# Sensor_Board.net
KiCad netlist of a schematic drawn in Altium Designer
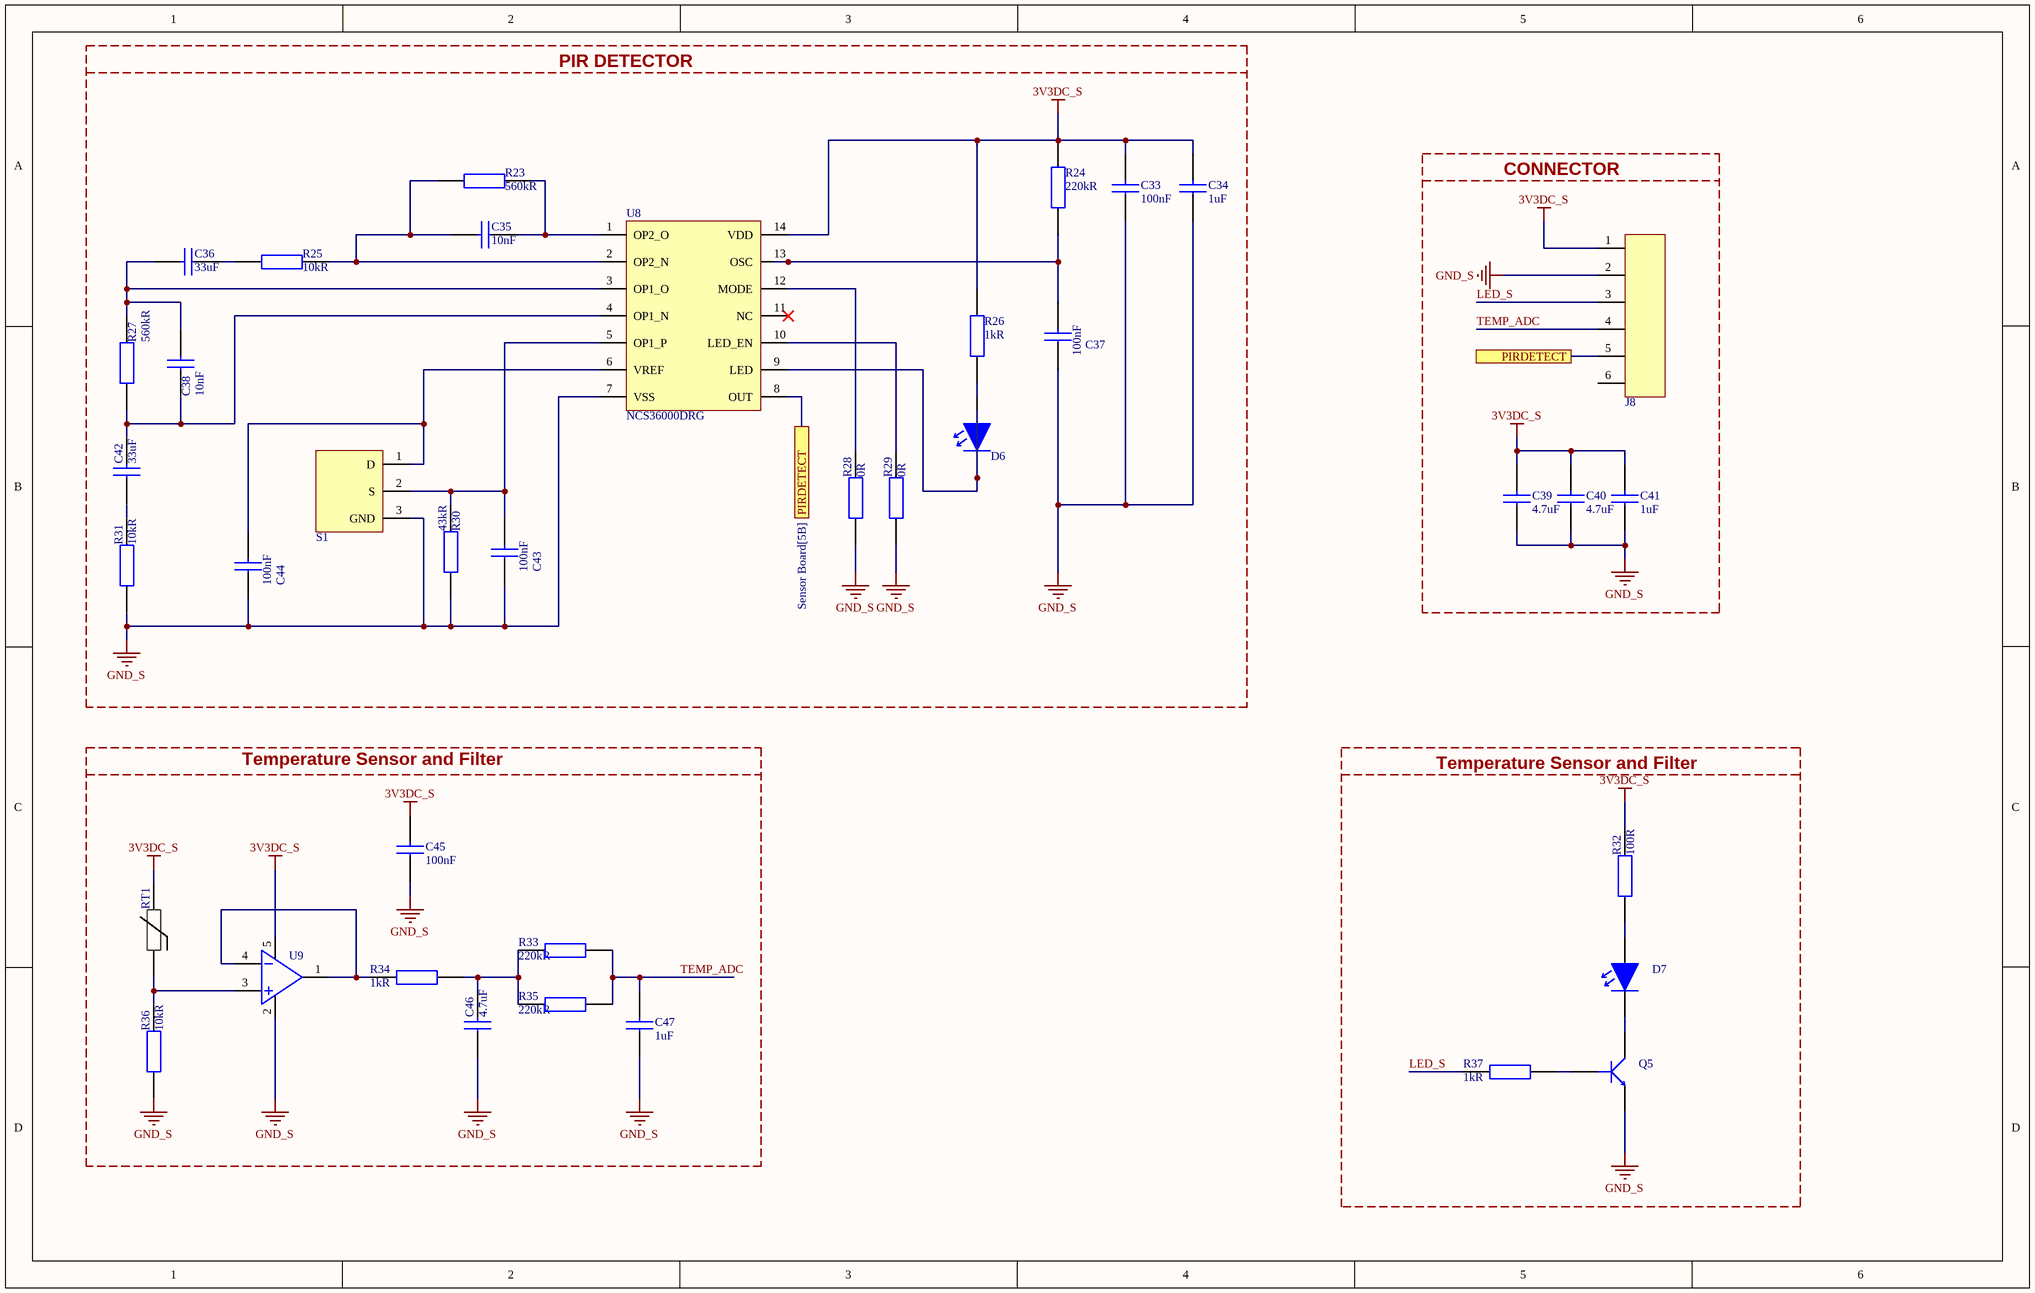
[diagram p0: Sensor Board.SchDoc]

(export (version "E")
  (design (tool "Eeschema 10.0.6"))
  (components
    (comp (ref "C33")
      (value "CL21B104KBCNNNC")
      (footprint "CAP_0805")
      (description "CAP CER 100nF %10 0805")
      (fields
        (field (name "MANUFACTURER") "Samsung")
        (field (name "TOLERANCE") "10%")
        (field (name "CAPACITANCE") "100nF")
        (field (name "DESIGNED BY") "Mustafa")
      )
      (libsource (lib "Mustafa_Library") (part "CAP CER 100nF 0805"))
    )
    (comp (ref "C34")
      (value "CL21B105KBFNNNE")
      (footprint "CAP_0805")
      (description "CAP CER 1uF %10 0805")
      (fields
        (field (name "MANUFACTURER") "Samsung")
        (field (name "TOLERANCE") "10%")
        (field (name "CAPACITANCE") "1uF")
        (field (name "DESIGNED BY") "Mustafa")
      )
      (libsource (lib "Mustafa_Library") (part "CAP CER 1uF 0805"))
    )
    (comp (ref "C35")
      (value "0603B103K160CT")
      (footprint "CAP_0603")
      (description "CAP CER 10nF %10 0603")
      (fields
        (field (name "MANUFACTURER") "Walsin Technologies")
        (field (name "TOLERANCE") "10%")
        (field (name "CAPACITANCE") "10nF")
        (field (name "DESIGNED BY") "Mustafa")
      )
      (libsource (lib "Mustafa_Library") (part "CAP CER 10nF 0603"))
    )
    (comp (ref "C36")
      (value "C3216X5R1E336M160AC")
      (footprint "CAP_1206")
      (description "CAP CER 33uF %20 1206 SMD")
      (fields
        (field (name "MANUFACTURER") "TDK")
        (field (name "TOLERANCE") "20%")
        (field (name "CAPACITANCE") "33uF")
        (field (name "DESIGNED BY") "Mustafa")
      )
      (libsource (lib "Mustafa_Library") (part "CAP CER 33uF 1206"))
    )
    (comp (ref "C37")
      (value "C0603C104K5RAC7867")
      (footprint "CAP_0603")
      (description "CAP CER 100nF %10 0603 SMD")
      (fields
        (field (name "MANUFACTURER") "KEMET")
        (field (name "MANUFACTURER PART NUMBER") "C0603C104K5RACTU")
        (field (name "DESIGNED BY") "Mustafa")
      )
      (libsource (lib "Mustafa_Library") (part "CAP CER 100nF 0603"))
    )
    (comp (ref "C38")
      (value "0603B103K160CT")
      (footprint "CAP_0603")
      (description "CAP CER 10nF %10 0603")
      (fields
        (field (name "MANUFACTURER") "Walsin Technologies")
        (field (name "TOLERANCE") "10%")
        (field (name "CAPACITANCE") "10nF")
        (field (name "DESIGNED BY") "Mustafa")
      )
      (libsource (lib "Mustafa_Library") (part "CAP CER 10nF 0603"))
    )
    (comp (ref "C39")
      (value "CL21A475KAQNNNE")
      (footprint "CAP_0805")
      (description "CAP CER 4.7uF %10 0805")
      (fields
        (field (name "MANUFACTURER") "Samsung")
        (field (name "TOLERANCE") "10%")
        (field (name "CAPACITANCE") "4.7uF")
        (field (name "DESIGNED BY") "Mustafa")
      )
      (libsource (lib "Mustafa_Library") (part "CAP CER 4.7uF 0805"))
    )
    (comp (ref "C40")
      (value "CL21A475KAQNNNE")
      (footprint "CAP_0805")
      (description "CAP CER 4.7uF %10 0805")
      (fields
        (field (name "MANUFACTURER") "Samsung")
        (field (name "TOLERANCE") "10%")
        (field (name "CAPACITANCE") "4.7uF")
        (field (name "DESIGNED BY") "Mustafa")
      )
      (libsource (lib "Mustafa_Library") (part "CAP CER 4.7uF 0805"))
    )
    (comp (ref "C41")
      (value "CL21B105KBFNNNE")
      (footprint "CAP_0805")
      (description "CAP CER 1uF %10 0805")
      (fields
        (field (name "MANUFACTURER") "Samsung")
        (field (name "TOLERANCE") "10%")
        (field (name "CAPACITANCE") "1uF")
        (field (name "DESIGNED BY") "Mustafa")
      )
      (libsource (lib "Mustafa_Library") (part "CAP CER 1uF 0805"))
    )
    (comp (ref "C42")
      (value "C3216X5R1E336M160AC")
      (footprint "CAP_1206")
      (description "CAP CER 33uF %20 1206 SMD")
      (fields
        (field (name "MANUFACTURER") "TDK")
        (field (name "TOLERANCE") "20%")
        (field (name "CAPACITANCE") "33uF")
        (field (name "DESIGNED BY") "Mustafa")
      )
      (libsource (lib "Mustafa_Library") (part "CAP CER 33uF 1206"))
    )
    (comp (ref "C43")
      (value "C0603C104K5RAC7867")
      (footprint "CAP_0603")
      (description "CAP CER 100nF %10 0603 SMD")
      (fields
        (field (name "MANUFACTURER") "KEMET")
        (field (name "MANUFACTURER PART NUMBER") "C0603C104K5RACTU")
        (field (name "DESIGNED BY") "Mustafa")
      )
      (libsource (lib "Mustafa_Library") (part "CAP CER 100nF 0603"))
    )
    (comp (ref "C44")
      (value "C0603C104K5RAC7867")
      (footprint "CAP_0603")
      (description "CAP CER 100nF %10 0603 SMD")
      (fields
        (field (name "MANUFACTURER") "KEMET")
        (field (name "MANUFACTURER PART NUMBER") "C0603C104K5RACTU")
        (field (name "DESIGNED BY") "Mustafa")
      )
      (libsource (lib "Mustafa_Library") (part "CAP CER 100nF 0603"))
    )
    (comp (ref "C45")
      (value "CL21B104KBCNNNC")
      (footprint "CAP_0805")
      (description "CAP CER 100nF %10 0805")
      (fields
        (field (name "MANUFACTURER") "Samsung")
        (field (name "TOLERANCE") "10%")
        (field (name "CAPACITANCE") "100nF")
        (field (name "DESIGNED BY") "Mustafa")
      )
      (libsource (lib "Mustafa_Library") (part "CAP CER 100nF 0805"))
    )
    (comp (ref "C46")
      (value "CL21A475KAQNNNE")
      (footprint "CAP_0805")
      (description "CAP CER 4.7uF %10 0805")
      (fields
        (field (name "MANUFACTURER") "Samsung")
        (field (name "TOLERANCE") "10%")
        (field (name "CAPACITANCE") "4.7uF")
        (field (name "DESIGNED BY") "Mustafa")
      )
      (libsource (lib "Mustafa_Library") (part "CAP CER 4.7uF 0805"))
    )
    (comp (ref "C47")
      (value "CL21B105KBFNNNE")
      (footprint "CAP_0805")
      (description "CAP CER 1uF %10 0805")
      (fields
        (field (name "MANUFACTURER") "Samsung")
        (field (name "TOLERANCE") "10%")
        (field (name "CAPACITANCE") "1uF")
        (field (name "DESIGNED BY") "Mustafa")
      )
      (libsource (lib "Mustafa_Library") (part "CAP CER 1uF 0805"))
    )
    (comp (ref "D6")
      (value "LTST-C171GKT")
      (footprint "LED_GREEN_0805")
      (description "Green 0805 130 º Min 5 mcd Typical 12 mcd Water Clear Lens SMT LED")
      (fields (field (name "MANUFACTURER") "Vishay Lite-On") (field (name "DESIGNED BY") "Mustafa"))
      (libsource (lib "Mustafa_Library") (part "LED GREEN 0805"))
    )
    (comp (ref "D7")
      (value "LH R974-LP-1")
      (footprint "LED_RED_0805")
      (description "LED Uni-Color Hyper Red 660nm 2-Pin Chip 0805(2012Metric) T/R")
      (fields (field (name "MANUFACTURER") "Osram Opto") (field (name "DESIGNED BY") "Mustafa"))
      (libsource (lib "Mustafa_Library") (part "LED RED 0805"))
    )
    (comp (ref "J8")
      (value "64800611622")
      (footprint "64800611622")
      (description "1.50mm 6PIN Connector")
      (fields (field (name "MANUFACTURER") "Wurth Electronics"))
      (libsource (lib "Mustafa_Library") (part "64800611622_conn_6pin"))
    )
    (comp (ref "Q5")
      (value "MMBT3904-7-F")
      (footprint "SOT-23F")
      (description "Transistor General Purpose BJT NPN 40 Volt 0.2A Automotive 3-Pin SOT-23")
      (fields (field (name "MANUFACTURER") "Diodes Zetex") (field (name "DESIGNED BY") "BERK"))
      (libsource (lib "Mustafa_Library") (part "MMBT3904-7-F"))
    )
    (comp (ref "R23")
      (value "RC0603JR-07560KL")
      (footprint "RES_0603")
      (description "RES SMD 560K OHM 5% 1/10W 0603")
      (fields
        (field (name "MANUFACTURER") "Yageo")
        (field (name "TOLERANCE") "5%")
        (field (name "RESISTANCE") "560kR")
        (field (name "DESIGNED BY") "BERK")
      )
      (libsource (lib "Mustafa_Library") (part "RES 560K OHM 0603"))
    )
    (comp (ref "R24")
      (value "RC0603JR-07220KL")
      (footprint "RES_0603")
      (description "RES 220K %5 OHM 0603 SMD")
      (fields
        (field (name "MANUFACTURER") "Yageo")
        (field (name "TOLERANCE") "5%")
        (field (name "RESISTANCE") "220kR")
      )
      (libsource (lib "") (part "RES 220K OHM 0603_1"))
    )
    (comp (ref "R25")
      (value "10kR")
      (footprint "RES_0603")
      (description "RES 10K %1 OHM 0603 SMD")
      (fields
        (field (name "MANUFACTURER") "Yageo")
        (field (name "MANUFACTURER PART NUMBER") "RC0603FR-0710KL")
        (field (name "DESIGNED BY") "Mustafa")
      )
      (libsource (lib "") (part "RES 10K OHM 0603_2"))
    )
    (comp (ref "R26")
      (value "RC0603FR-0710KL")
      (footprint "RES_0603")
      (description "RES 1K %1 OHM 0603 SMD")
      (fields
        (field (name "MANUFACTURER") "Yageo")
        (field (name "MANUFACTURER PART NUMBER") "RC0603JR-071KL")
        (field (name "RESISTANCE") "1kR")
        (field (name "DESIGNED BY") "BERK")
      )
      (libsource (lib "") (part "RES 1K OHM 0603_1"))
    )
    (comp (ref "R27")
      (value "RC0603JR-07560KL")
      (footprint "RES_0603")
      (description "RES SMD 560K OHM 5% 1/10W 0603")
      (fields
        (field (name "MANUFACTURER") "Yageo")
        (field (name "TOLERANCE") "5%")
        (field (name "RESISTANCE") "560kR")
        (field (name "DESIGNED BY") "BERK")
      )
      (libsource (lib "") (part "RES 560K OHM 0603_1"))
    )
    (comp (ref "R28")
      (value "RC0603JR-070RL")
      (footprint "RES_0603")
      (description "RES 0 %1 OHM 0603 SMD")
      (fields
        (field (name "MANUFACTURER") "Yageo")
        (field (name "TOLERANCE") "1%")
        (field (name "RESISTANCE") "0R")
        (field (name "DESIGNED BY") "BERK")
      )
      (libsource (lib "Mustafa_Library") (part "RES 0 OHM 0603"))
    )
    (comp (ref "R29")
      (value "RC0603JR-070RL")
      (footprint "RES_0603")
      (description "RES 0 %1 OHM 0603 SMD")
      (fields
        (field (name "MANUFACTURER") "Yageo")
        (field (name "TOLERANCE") "1%")
        (field (name "RESISTANCE") "0R")
        (field (name "DESIGNED BY") "BERK")
      )
      (libsource (lib "Mustafa_Library") (part "RES 0 OHM 0603"))
    )
    (comp (ref "R30")
      (value "RC0603JR-0743KL")
      (footprint "RES_0603")
      (description "RES 43K %5 OHM 0603 SMD")
      (fields
        (field (name "MANUFACTURER") "Yageo")
        (field (name "TOLERANCE") "5%")
        (field (name "RESISTANCE") "43kR")
        (field (name "DESIGNED BY") "BERK")
      )
      (libsource (lib "Mustafa_Library") (part "RES 43K OHM 0603"))
    )
    (comp (ref "R31")
      (value "10kR")
      (footprint "RES_0603")
      (description "RES 10K %1 OHM 0603 SMD")
      (fields
        (field (name "MANUFACTURER") "Yageo")
        (field (name "MANUFACTURER PART NUMBER") "RC0603FR-0710KL")
        (field (name "DESIGNED BY") "Mustafa")
      )
      (libsource (lib "") (part "RES 10K OHM 0603_1"))
    )
    (comp (ref "R32")
      (value "RC0603JR-07100RL")
      (footprint "RES_0603")
      (description "RES 100 %5 OHM 0603 SMD")
      (fields
        (field (name "MANUFACTURER") "Yageo")
        (field (name "TOLERANCE") "5%")
        (field (name "RESISTANCE") "100R")
        (field (name "DESIGNED BY") "BERK")
      )
      (libsource (lib "Mustafa_Library") (part "RES 100 OHM 0603"))
    )
    (comp (ref "R33")
      (value "RC0603JR-07220KL")
      (footprint "RES_0603")
      (description "RES 220K %5 OHM 0603 SMD")
      (fields
        (field (name "MANUFACTURER") "Yageo")
        (field (name "TOLERANCE") "5%")
        (field (name "RESISTANCE") "220kR")
      )
      (libsource (lib "Mustafa_Library") (part "RES 220K OHM 0603"))
    )
    (comp (ref "R34")
      (value "RC0603FR-0710KL")
      (footprint "RES_0603")
      (description "RES 1K %1 OHM 0603 SMD")
      (fields
        (field (name "MANUFACTURER") "Yageo")
        (field (name "MANUFACTURER PART NUMBER") "RC0603JR-071KL")
        (field (name "RESISTANCE") "1kR")
        (field (name "DESIGNED BY") "BERK")
      )
      (libsource (lib "Mustafa_Library") (part "RES 1K OHM 0603"))
    )
    (comp (ref "R35")
      (value "RC0603JR-07220KL")
      (footprint "RES_0603")
      (description "RES 220K %5 OHM 0603 SMD")
      (fields
        (field (name "MANUFACTURER") "Yageo")
        (field (name "TOLERANCE") "5%")
        (field (name "RESISTANCE") "220kR")
      )
      (libsource (lib "Mustafa_Library") (part "RES 220K OHM 0603"))
    )
    (comp (ref "R36")
      (value "10kR")
      (footprint "RES_0603")
      (description "RES 10K %1 OHM 0603 SMD")
      (fields
        (field (name "MANUFACTURER") "Yageo")
        (field (name "MANUFACTURER PART NUMBER") "RC0603FR-0710KL")
        (field (name "DESIGNED BY") "Mustafa")
      )
      (libsource (lib "Mustafa_Library") (part "RES 10K OHM 0603"))
    )
    (comp (ref "R37")
      (value "RC0603FR-0710KL")
      (footprint "RES_0603")
      (description "RES 1K %1 OHM 0603 SMD")
      (fields
        (field (name "MANUFACTURER") "Yageo")
        (field (name "MANUFACTURER PART NUMBER") "RC0603JR-071KL")
        (field (name "RESISTANCE") "1kR")
        (field (name "DESIGNED BY") "BERK")
      )
      (libsource (lib "Mustafa_Library") (part "RES 1K OHM 0603"))
    )
    (comp (ref "RT1")
      (value "TFPT1206L1002FM")
      (footprint "RES_1206")
      (description "Thermistor PTC 10K Ohm 1% 1206")
      (fields
        (field (name "MANUFACTURER") "Vishay Dale")
        (field (name "TOLERANCE") "1%")
        (field (name "DESIGNED BY") "Mustafa")
      )
      (libsource (lib "Mustafa_Library") (part "TFPT1206L1002FM"))
    )
    (comp (ref "S1")
      (value "LHI 878/3902")
      (footprint "LHI 878")
      (description "SENSOR PYRO DETECTOR DUAL MOTION")
      (fields (field (name "DESIGNED BY") "Mustafa"))
      (libsource (lib "Mustafa_Library") (part "LHI 878/3902"))
    )
    (comp (ref "U8")
      (value "NCS36000DRG")
      (footprint "SOIC14")
      (description "PIR Controller Low Noise Amplifiers and LDO Regulator 14-Pin SOIC N T/R")
      (fields (field (name "MANUFACTURER") "ON Semiconductor") (field (name "DESIGNED BY") "Mustafa"))
      (libsource (lib "Mustafa_Library") (part "NCS36000"))
    )
    (comp (ref "U9")
      (value "OPA314AIDBVR")
      (footprint "SOT23-5")
      (description "Op Amp OPA314")
      (fields (field (name "MANUFACTURER") "Texas Instruments") (field (name "DESIGNED BY") "BERK"))
      (libsource (lib "Mustafa_Library") (part "OPA314"))
    )
  )
  (nets
    (net (code "1") (name "/LED_S") (class "Default")
      (node (ref "J8") (pin "3") (pintype "power_in"))
      (node (ref "R37") (pin "1") (pinfunction "1_1") (pintype "passive"))
    )
    (net (code "2") (name "/PIRDETECT") (class "Default")
      (node (ref "J8") (pin "5") (pintype "power_in"))
      (node (ref "U8") (pin "8") (pinfunction "OUT_8") (pintype "passive"))
    )
    (net (code "3") (name "/TEMP_ADC") (class "Default")
      (node (ref "C47") (pin "2") (pinfunction "2_2") (pintype "passive"))
      (node (ref "J8") (pin "4") (pintype "power_in"))
      (node (ref "R33") (pin "2") (pinfunction "2_2") (pintype "passive"))
      (node (ref "R35") (pin "2") (pinfunction "2_2") (pintype "passive"))
    )
    (net (code "4") (name "3V3DC_S") (class "Default")
      (node (ref "C33") (pin "2") (pinfunction "2_2") (pintype "passive"))
      (node (ref "C34") (pin "2") (pinfunction "2_2") (pintype "passive"))
      (node (ref "C39") (pin "2") (pinfunction "2_2") (pintype "passive"))
      (node (ref "C40") (pin "2") (pinfunction "2_2") (pintype "passive"))
      (node (ref "C41") (pin "2") (pinfunction "2_2") (pintype "passive"))
      (node (ref "C45") (pin "2") (pinfunction "2_2") (pintype "passive"))
      (node (ref "J8") (pin "1") (pintype "power_in"))
      (node (ref "R24") (pin "2") (pinfunction "2_2") (pintype "passive"))
      (node (ref "R26") (pin "2") (pinfunction "2_2") (pintype "passive"))
      (node (ref "R32") (pin "2") (pinfunction "2_2") (pintype "passive"))
      (node (ref "RT1") (pin "2") (pinfunction "2_2") (pintype "passive"))
      (node (ref "U8") (pin "14") (pinfunction "VDD_14") (pintype "passive"))
      (node (ref "U9") (pin "5") (pinfunction "5_5") (pintype "passive"))
    )
    (net (code "5") (name "GND_S") (class "Default")
      (node (ref "C33") (pin "1") (pinfunction "1_1") (pintype "passive"))
      (node (ref "C34") (pin "1") (pinfunction "1_1") (pintype "passive"))
      (node (ref "C37") (pin "1") (pinfunction "1_1") (pintype "passive"))
      (node (ref "C39") (pin "1") (pinfunction "1_1") (pintype "passive"))
      (node (ref "C40") (pin "1") (pinfunction "1_1") (pintype "passive"))
      (node (ref "C41") (pin "1") (pinfunction "1_1") (pintype "passive"))
      (node (ref "C43") (pin "1") (pinfunction "1_1") (pintype "passive"))
      (node (ref "C44") (pin "1") (pinfunction "1_1") (pintype "passive"))
      (node (ref "C45") (pin "1") (pinfunction "1_1") (pintype "passive"))
      (node (ref "C46") (pin "1") (pinfunction "1_1") (pintype "passive"))
      (node (ref "C47") (pin "1") (pinfunction "1_1") (pintype "passive"))
      (node (ref "J8") (pin "2") (pintype "power_in"))
      (node (ref "Q5") (pin "2") (pinfunction "E_2") (pintype "power_in"))
      (node (ref "R28") (pin "1") (pinfunction "1_1") (pintype "passive"))
      (node (ref "R29") (pin "1") (pinfunction "1_1") (pintype "passive"))
      (node (ref "R30") (pin "1") (pinfunction "1_1") (pintype "passive"))
      (node (ref "R31") (pin "2") (pinfunction "2_2") (pintype "passive"))
      (node (ref "R36") (pin "1") (pinfunction "1_1") (pintype "passive"))
      (node (ref "S1") (pin "3") (pinfunction "GND_3") (pintype "passive"))
      (node (ref "U8") (pin "7") (pinfunction "VSS_7") (pintype "passive"))
      (node (ref "U9") (pin "2") (pinfunction "2_2") (pintype "passive"))
    )
    (net (code "6") (name "Net-(C36-Pad1)") (class "Default")
      (node (ref "C36") (pin "1") (pinfunction "1_1") (pintype "passive"))
      (node (ref "R25") (pin "1") (pinfunction "1_1") (pintype "passive"))
    )
    (net (code "7") (name "Net-(C42-Pad1)") (class "Default")
      (node (ref "C42") (pin "1") (pinfunction "1_1") (pintype "passive"))
      (node (ref "R31") (pin "1") (pinfunction "1_1") (pintype "passive"))
    )
    (net (code "8") (name "Net-(C46-Pad2)") (class "Default")
      (node (ref "C46") (pin "2") (pinfunction "2_2") (pintype "passive"))
      (node (ref "R33") (pin "1") (pinfunction "1_1") (pintype "passive"))
      (node (ref "R34") (pin "2") (pinfunction "2_2") (pintype "passive"))
      (node (ref "R35") (pin "1") (pinfunction "1_1") (pintype "passive"))
    )
    (net (code "9") (name "Net-(D6-Pad2)") (class "Default")
      (node (ref "D6") (pin "2") (pinfunction "2_2") (pintype "power_in"))
      (node (ref "R26") (pin "1") (pinfunction "1_1") (pintype "passive"))
    )
    (net (code "10") (name "Net-(D7-Pad2)") (class "Default")
      (node (ref "D7") (pin "2") (pinfunction "2_2") (pintype "power_in"))
      (node (ref "R32") (pin "1") (pinfunction "1_1") (pintype "passive"))
    )
    (net (code "11") (name "Net-(Q5-B)") (class "Default")
      (node (ref "Q5") (pin "1") (pinfunction "B_1") (pintype "power_in"))
      (node (ref "R37") (pin "2") (pinfunction "2_2") (pintype "passive"))
    )
    (net (code "12") (name "Net-(Q5-C)") (class "Default")
      (node (ref "D7") (pin "1") (pinfunction "1_1") (pintype "power_in"))
      (node (ref "Q5") (pin "3") (pinfunction "C_3") (pintype "power_in"))
    )
    (net (code "13") (name "Net-(R34-Pad1)") (class "Default")
      (node (ref "R34") (pin "1") (pinfunction "1_1") (pintype "passive"))
      (node (ref "U9") (pin "1") (pinfunction "1_1") (pintype "passive"))
      (node (ref "U9") (pin "4") (pinfunction "4_4") (pintype "passive"))
    )
    (net (code "14") (name "Net-(R36-Pad2)") (class "Default")
      (node (ref "R36") (pin "2") (pinfunction "2_2") (pintype "passive"))
      (node (ref "RT1") (pin "1") (pinfunction "1_1") (pintype "passive"))
      (node (ref "U9") (pin "3") (pinfunction "3_3") (pintype "passive"))
    )
    (net (code "15") (name "Net-(S1-D)") (class "Default")
      (node (ref "C44") (pin "2") (pinfunction "2_2") (pintype "passive"))
      (node (ref "S1") (pin "1") (pinfunction "D_1") (pintype "passive"))
      (node (ref "U8") (pin "6") (pinfunction "VREF_6") (pintype "passive"))
    )
    (net (code "16") (name "Net-(S1-S)") (class "Default")
      (node (ref "C43") (pin "2") (pinfunction "2_2") (pintype "passive"))
      (node (ref "R30") (pin "2") (pinfunction "2_2") (pintype "passive"))
      (node (ref "S1") (pin "2") (pinfunction "S_2") (pintype "passive"))
      (node (ref "U8") (pin "5") (pinfunction "OP1_P_5") (pintype "passive"))
    )
    (net (code "17") (name "Net-(U8-LED)") (class "Default")
      (node (ref "D6") (pin "1") (pinfunction "1_1") (pintype "power_in"))
      (node (ref "U8") (pin "9") (pinfunction "LED_9") (pintype "passive"))
    )
    (net (code "18") (name "Net-(U8-LED_EN)") (class "Default")
      (node (ref "R29") (pin "2") (pinfunction "2_2") (pintype "passive"))
      (node (ref "U8") (pin "10") (pinfunction "LED_EN_10") (pintype "passive"))
    )
    (net (code "19") (name "Net-(U8-MODE)") (class "Default")
      (node (ref "R28") (pin "2") (pinfunction "2_2") (pintype "passive"))
      (node (ref "U8") (pin "12") (pinfunction "MODE_12") (pintype "passive"))
    )
    (net (code "20") (name "Net-(U8-OP1_N)") (class "Default")
      (node (ref "C38") (pin "1") (pinfunction "1_1") (pintype "passive"))
      (node (ref "C42") (pin "2") (pinfunction "2_2") (pintype "passive"))
      (node (ref "R27") (pin "2") (pinfunction "2_2") (pintype "passive"))
      (node (ref "U8") (pin "4") (pinfunction "OP1_N_4") (pintype "passive"))
    )
    (net (code "21") (name "Net-(U8-OP1_O)") (class "Default")
      (node (ref "C36") (pin "2") (pinfunction "2_2") (pintype "passive"))
      (node (ref "C38") (pin "2") (pinfunction "2_2") (pintype "passive"))
      (node (ref "R27") (pin "1") (pinfunction "1_1") (pintype "passive"))
      (node (ref "U8") (pin "3") (pinfunction "OP1_O_3") (pintype "passive"))
    )
    (net (code "22") (name "Net-(U8-OP2_N)") (class "Default")
      (node (ref "C35") (pin "2") (pinfunction "2_2") (pintype "passive"))
      (node (ref "R23") (pin "1") (pinfunction "1_1") (pintype "passive"))
      (node (ref "R25") (pin "2") (pinfunction "2_2") (pintype "passive"))
      (node (ref "U8") (pin "2") (pinfunction "OP2_N_2") (pintype "passive"))
    )
    (net (code "23") (name "Net-(U8-OP2_O)") (class "Default")
      (node (ref "C35") (pin "1") (pinfunction "1_1") (pintype "passive"))
      (node (ref "R23") (pin "2") (pinfunction "2_2") (pintype "passive"))
      (node (ref "U8") (pin "1") (pinfunction "OP2_O_1") (pintype "passive"))
    )
    (net (code "24") (name "Net-(U8-OSC)") (class "Default")
      (node (ref "C37") (pin "2") (pinfunction "2_2") (pintype "passive"))
      (node (ref "R24") (pin "1") (pinfunction "1_1") (pintype "passive"))
      (node (ref "U8") (pin "13") (pinfunction "OSC_13") (pintype "passive"))
    )
    (net (code "25") (name "unconnected-(J8-Pad6)") (class "Default")
      (node (ref "J8") (pin "6") (pintype "power_in"))
    )
    (net (code "26") (name "unconnected-(U8-NC-Pad11)") (class "Default")
      (node (ref "U8") (pin "11") (pinfunction "NC_11") (pintype "passive+no_connect"))
    )
  )
)
